# SCH_Cocktail-Hat-Screw-Terminals_2026-04.net
KiCad netlist of a schematic drawn in EasyEDA
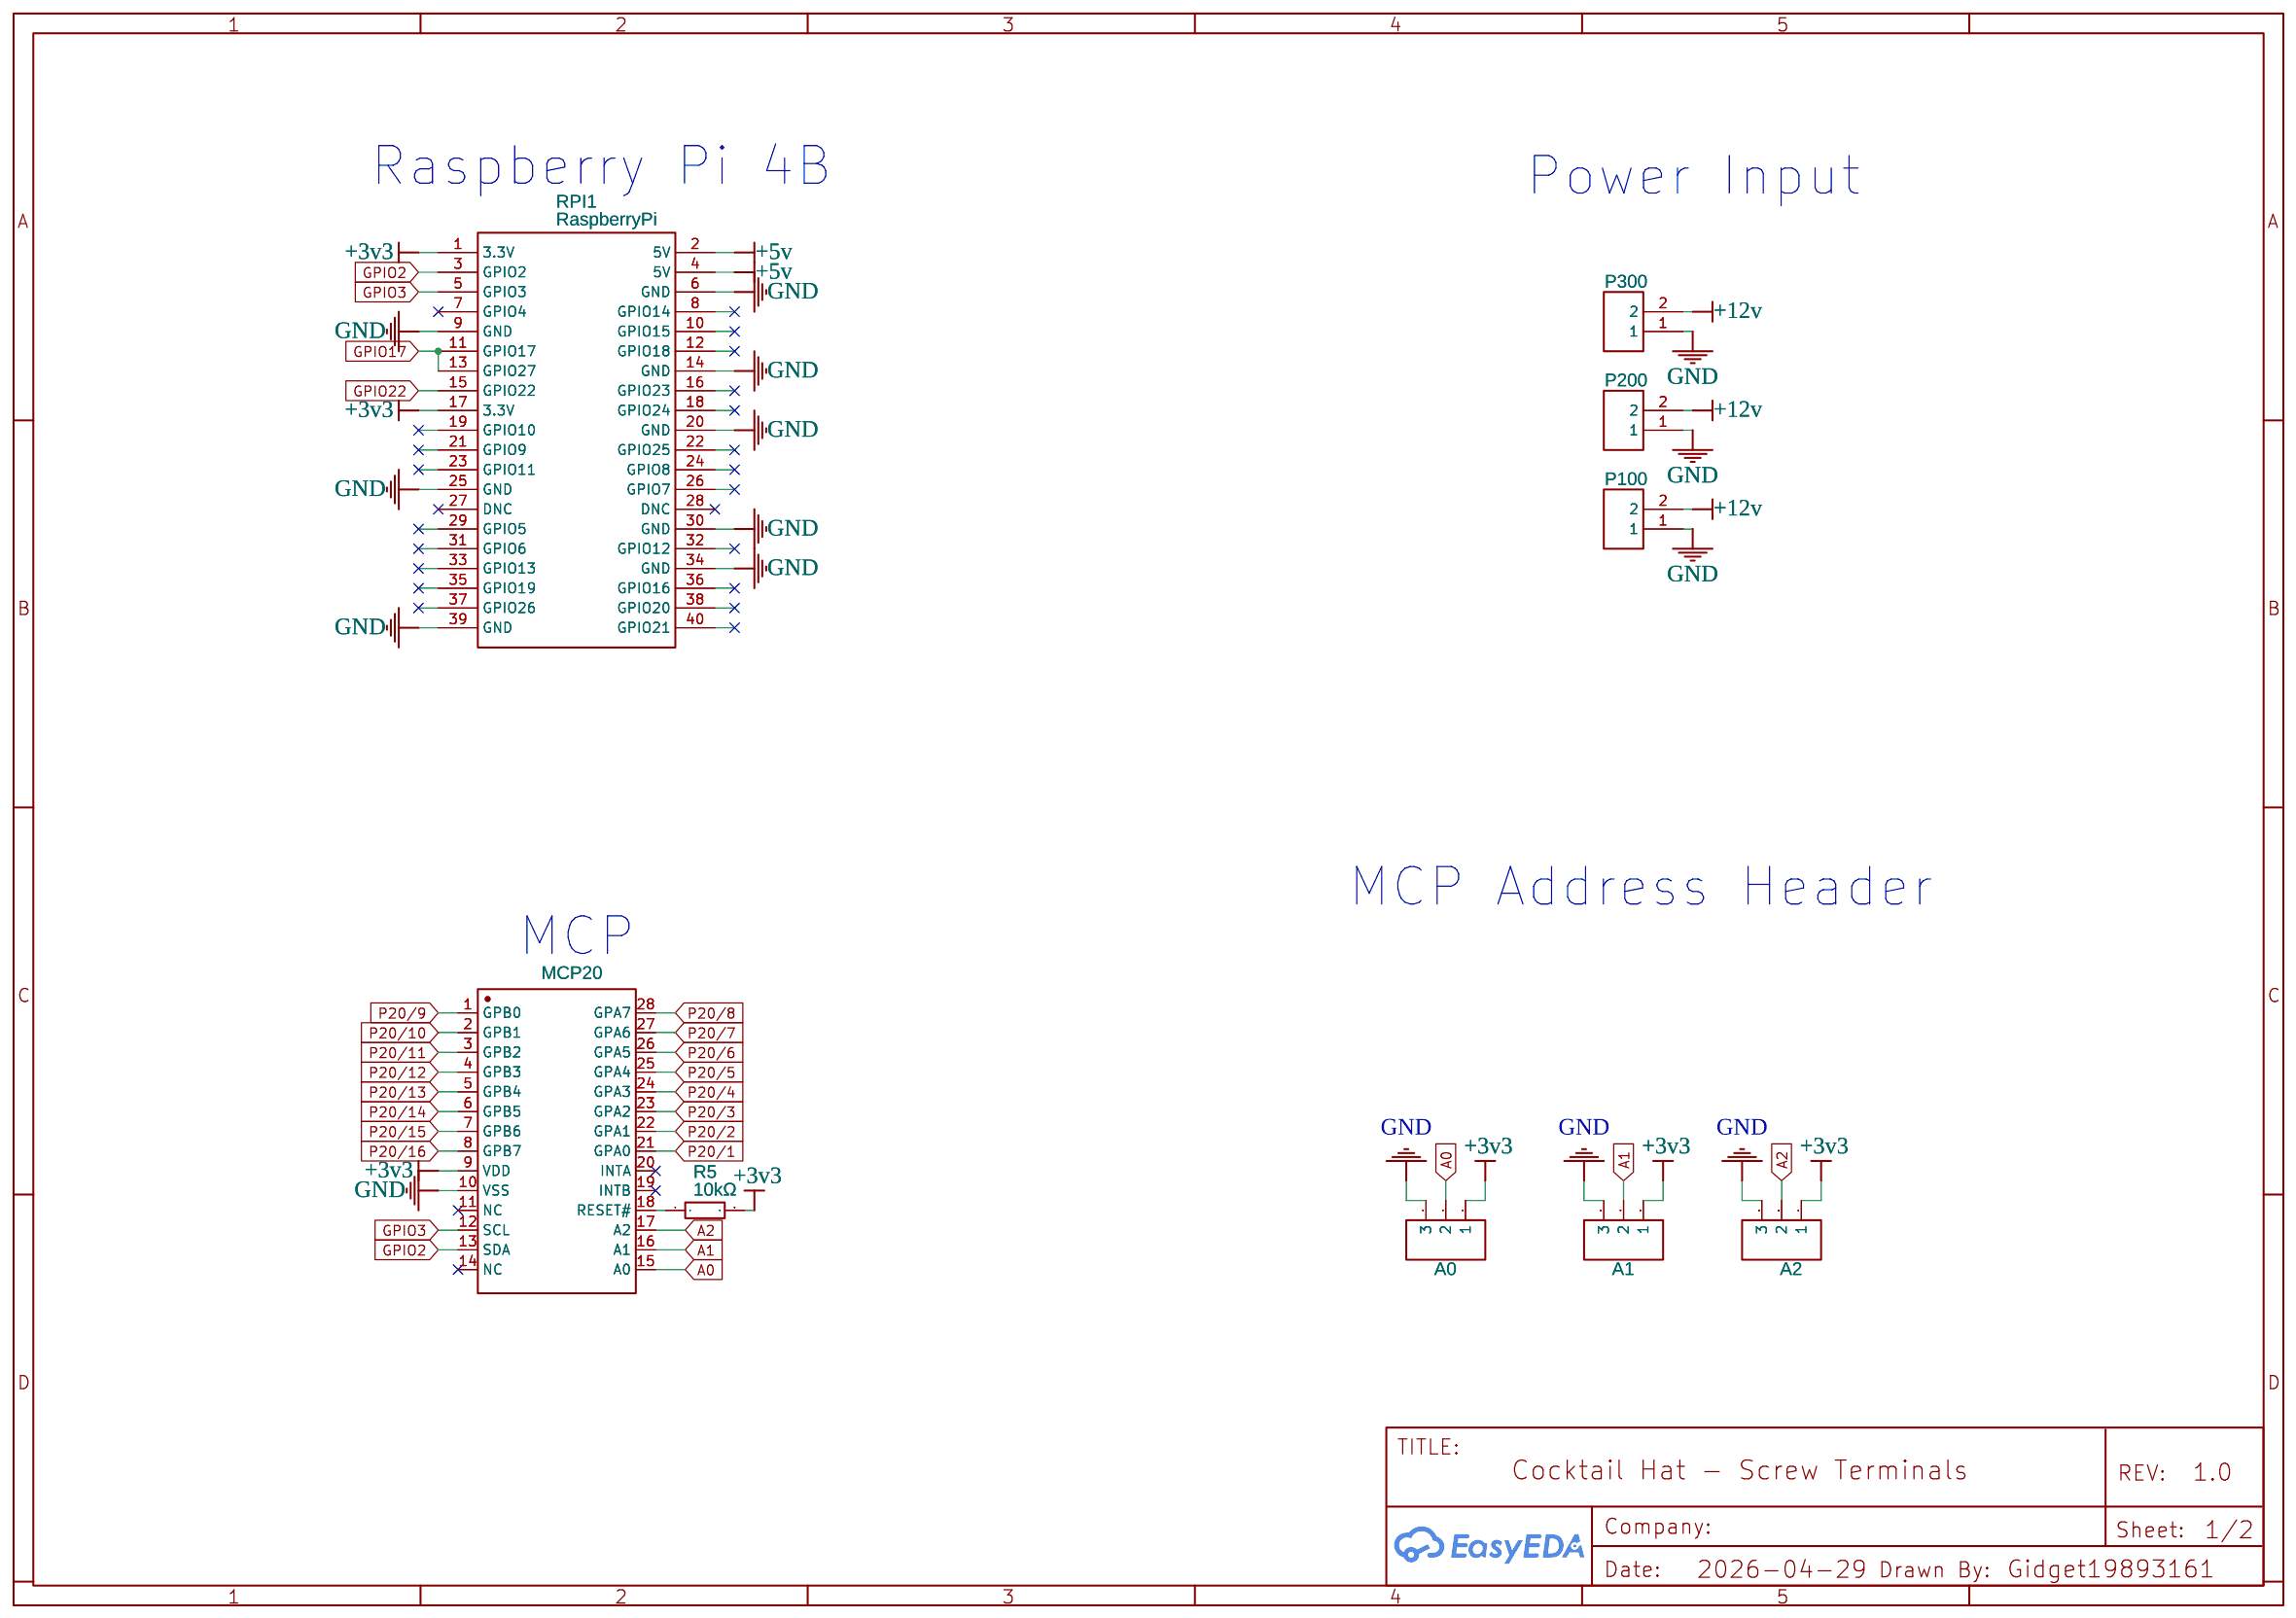
[diagram p0: Main]
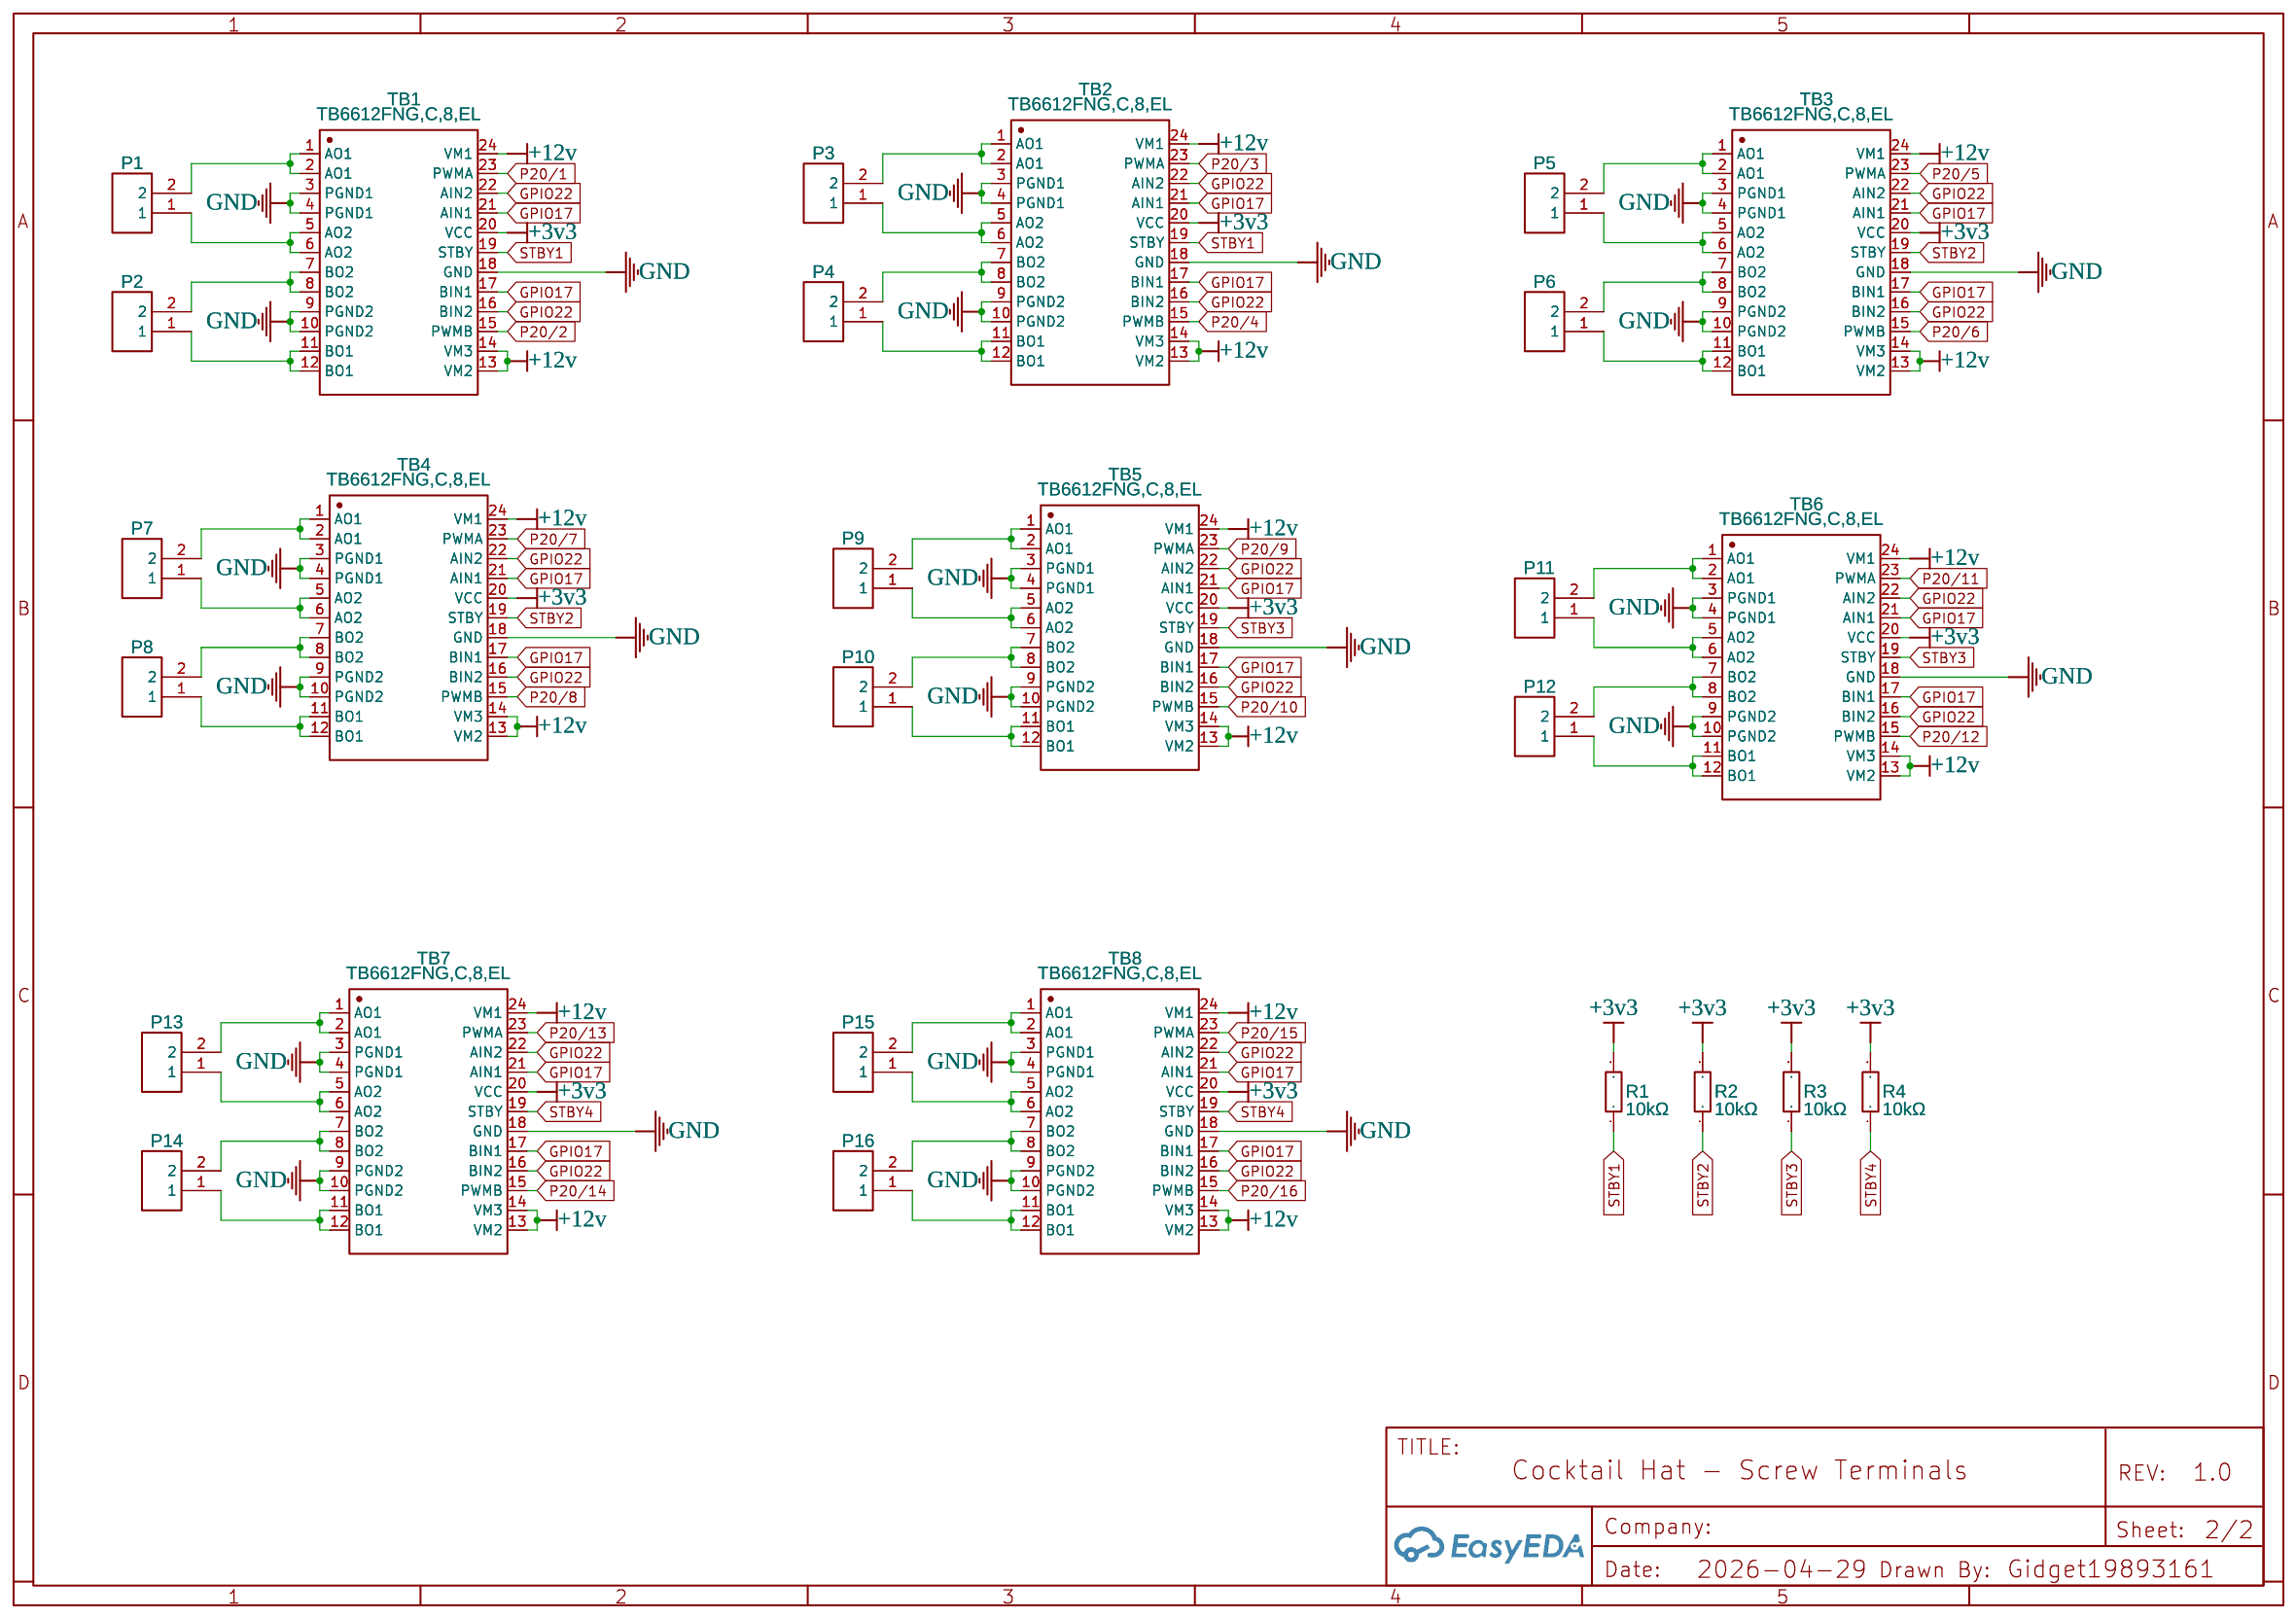
[diagram p1: TB20]

(export (version "E")
  (design (tool "Eeschema 10.0.6"))
  (components
    (comp (ref "A0")
      (value "Header-Male-2.54_1x3")
      (fields (field (name "Manufacturer Part") "2.54-1*3P针") (field (name "Manufacturer") "BOOMELE(博穆精密)"))
      (libsource (lib "") (part "Header-Male-2.54_1x3"))
    )
    (comp (ref "A1")
      (value "Header-Male-2.54_1x3")
      (fields (field (name "Manufacturer Part") "2.54-1*3P针") (field (name "Manufacturer") "BOOMELE(博穆精密)"))
      (libsource (lib "") (part "Header-Male-2.54_1x3"))
    )
    (comp (ref "A2")
      (value "Header-Male-2.54_1x3")
      (fields (field (name "Manufacturer Part") "2.54-1*3P针") (field (name "Manufacturer") "BOOMELE(博穆精密)"))
      (libsource (lib "") (part "Header-Male-2.54_1x3"))
    )
    (comp (ref "MCP20")
      (value "MCP23017-E/SO")
      (fields (field (name "Manufacturer") "MICROCHIP(美国微芯)"))
      (libsource (lib "") (part "MCP23017-E/SO"))
    )
    (comp (ref "P100")
      (value "WJ500V-5.08-2P-14-00A")
      (fields
        (field (name "Manufacturer Part") "WJ500V-5.08-2P")
        (field (name "Manufacturer") "KANGNEX(康奈克斯电气)")
      )
      (libsource (lib "") (part "WJ500V-5.08-2P-14-00A"))
    )
    (comp (ref "P200")
      (value "WJ500V-5.08-2P-14-00A")
      (fields
        (field (name "Manufacturer Part") "WJ500V-5.08-2P")
        (field (name "Manufacturer") "KANGNEX(康奈克斯电气)")
      )
      (libsource (lib "") (part "WJ500V-5.08-2P-14-00A"))
    )
    (comp (ref "P300")
      (value "WJ500V-5.08-2P-14-00A")
      (fields
        (field (name "Manufacturer Part") "WJ500V-5.08-2P")
        (field (name "Manufacturer") "KANGNEX(康奈克斯电气)")
      )
      (libsource (lib "") (part "WJ500V-5.08-2P-14-00A"))
    )
    (comp (ref "R5")
      (value "10kΩ")
      (fields
        (field (name "Manufacturer Part") "1206W4F1002T5E")
        (field (name "Manufacturer") "UNI-ROYAL(厚声)")
      )
      (libsource (lib "") (part "1206W4F1002T5E"))
    )
    (comp (ref "RPI1") (value "RaspberryPi") (libsource (lib "") (part "RaspberryPi")))
    (comp (ref "P1")
      (value "WJ500V-5.08-2P-14-00A")
      (fields
        (field (name "Manufacturer Part") "WJ500V-5.08-2P")
        (field (name "Manufacturer") "KANGNEX(康奈克斯电气)")
      )
      (libsource (lib "") (part "WJ500V-5.08-2P-14-00A"))
    )
    (comp (ref "P2")
      (value "WJ500V-5.08-2P-14-00A")
      (fields
        (field (name "Manufacturer Part") "WJ500V-5.08-2P")
        (field (name "Manufacturer") "KANGNEX(康奈克斯电气)")
      )
      (libsource (lib "") (part "WJ500V-5.08-2P-14-00A"))
    )
    (comp (ref "P3")
      (value "WJ500V-5.08-2P-14-00A")
      (fields
        (field (name "Manufacturer Part") "WJ500V-5.08-2P")
        (field (name "Manufacturer") "KANGNEX(康奈克斯电气)")
      )
      (libsource (lib "") (part "WJ500V-5.08-2P-14-00A"))
    )
    (comp (ref "P4")
      (value "WJ500V-5.08-2P-14-00A")
      (fields
        (field (name "Manufacturer Part") "WJ500V-5.08-2P")
        (field (name "Manufacturer") "KANGNEX(康奈克斯电气)")
      )
      (libsource (lib "") (part "WJ500V-5.08-2P-14-00A"))
    )
    (comp (ref "P5")
      (value "WJ500V-5.08-2P-14-00A")
      (fields
        (field (name "Manufacturer Part") "WJ500V-5.08-2P")
        (field (name "Manufacturer") "KANGNEX(康奈克斯电气)")
      )
      (libsource (lib "") (part "WJ500V-5.08-2P-14-00A"))
    )
    (comp (ref "P6")
      (value "WJ500V-5.08-2P-14-00A")
      (fields
        (field (name "Manufacturer Part") "WJ500V-5.08-2P")
        (field (name "Manufacturer") "KANGNEX(康奈克斯电气)")
      )
      (libsource (lib "") (part "WJ500V-5.08-2P-14-00A"))
    )
    (comp (ref "P7")
      (value "WJ500V-5.08-2P-14-00A")
      (fields
        (field (name "Manufacturer Part") "WJ500V-5.08-2P")
        (field (name "Manufacturer") "KANGNEX(康奈克斯电气)")
      )
      (libsource (lib "") (part "WJ500V-5.08-2P-14-00A"))
    )
    (comp (ref "P8")
      (value "WJ500V-5.08-2P-14-00A")
      (fields
        (field (name "Manufacturer Part") "WJ500V-5.08-2P")
        (field (name "Manufacturer") "KANGNEX(康奈克斯电气)")
      )
      (libsource (lib "") (part "WJ500V-5.08-2P-14-00A"))
    )
    (comp (ref "P9")
      (value "WJ500V-5.08-2P-14-00A")
      (fields
        (field (name "Manufacturer Part") "WJ500V-5.08-2P")
        (field (name "Manufacturer") "KANGNEX(康奈克斯电气)")
      )
      (libsource (lib "") (part "WJ500V-5.08-2P-14-00A"))
    )
    (comp (ref "P10")
      (value "WJ500V-5.08-2P-14-00A")
      (fields
        (field (name "Manufacturer Part") "WJ500V-5.08-2P")
        (field (name "Manufacturer") "KANGNEX(康奈克斯电气)")
      )
      (libsource (lib "") (part "WJ500V-5.08-2P-14-00A"))
    )
    (comp (ref "P11")
      (value "WJ500V-5.08-2P-14-00A")
      (fields
        (field (name "Manufacturer Part") "WJ500V-5.08-2P")
        (field (name "Manufacturer") "KANGNEX(康奈克斯电气)")
      )
      (libsource (lib "") (part "WJ500V-5.08-2P-14-00A"))
    )
    (comp (ref "P12")
      (value "WJ500V-5.08-2P-14-00A")
      (fields
        (field (name "Manufacturer Part") "WJ500V-5.08-2P")
        (field (name "Manufacturer") "KANGNEX(康奈克斯电气)")
      )
      (libsource (lib "") (part "WJ500V-5.08-2P-14-00A"))
    )
    (comp (ref "P13")
      (value "WJ500V-5.08-2P-14-00A")
      (fields
        (field (name "Manufacturer Part") "WJ500V-5.08-2P")
        (field (name "Manufacturer") "KANGNEX(康奈克斯电气)")
      )
      (libsource (lib "") (part "WJ500V-5.08-2P-14-00A"))
    )
    (comp (ref "P14")
      (value "WJ500V-5.08-2P-14-00A")
      (fields
        (field (name "Manufacturer Part") "WJ500V-5.08-2P")
        (field (name "Manufacturer") "KANGNEX(康奈克斯电气)")
      )
      (libsource (lib "") (part "WJ500V-5.08-2P-14-00A"))
    )
    (comp (ref "P15")
      (value "WJ500V-5.08-2P-14-00A")
      (fields
        (field (name "Manufacturer Part") "WJ500V-5.08-2P")
        (field (name "Manufacturer") "KANGNEX(康奈克斯电气)")
      )
      (libsource (lib "") (part "WJ500V-5.08-2P-14-00A"))
    )
    (comp (ref "P16")
      (value "WJ500V-5.08-2P-14-00A")
      (fields
        (field (name "Manufacturer Part") "WJ500V-5.08-2P")
        (field (name "Manufacturer") "KANGNEX(康奈克斯电气)")
      )
      (libsource (lib "") (part "WJ500V-5.08-2P-14-00A"))
    )
    (comp (ref "R1")
      (value "10kΩ")
      (fields
        (field (name "Manufacturer Part") "1206W4F1002T5E")
        (field (name "Manufacturer") "UNI-ROYAL(厚声)")
      )
      (libsource (lib "") (part "1206W4F1002T5E"))
    )
    (comp (ref "R2")
      (value "10kΩ")
      (fields
        (field (name "Manufacturer Part") "1206W4F1002T5E")
        (field (name "Manufacturer") "UNI-ROYAL(厚声)")
      )
      (libsource (lib "") (part "1206W4F1002T5E"))
    )
    (comp (ref "R3")
      (value "10kΩ")
      (fields
        (field (name "Manufacturer Part") "1206W4F1002T5E")
        (field (name "Manufacturer") "UNI-ROYAL(厚声)")
      )
      (libsource (lib "") (part "1206W4F1002T5E"))
    )
    (comp (ref "R4")
      (value "10kΩ")
      (fields
        (field (name "Manufacturer Part") "1206W4F1002T5E")
        (field (name "Manufacturer") "UNI-ROYAL(厚声)")
      )
      (libsource (lib "") (part "1206W4F1002T5E"))
    )
    (comp (ref "TB1")
      (value "TB6612FNG,C,8,EL")
      (fields (field (name "Manufacturer") "TOSHIBA(东芝)"))
      (libsource (lib "") (part "TB6612FNG,C,8,EL"))
    )
    (comp (ref "TB2")
      (value "TB6612FNG,C,8,EL")
      (fields (field (name "Manufacturer") "TOSHIBA(东芝)"))
      (libsource (lib "") (part "TB6612FNG,C,8,EL"))
    )
    (comp (ref "TB3")
      (value "TB6612FNG,C,8,EL")
      (fields (field (name "Manufacturer") "TOSHIBA(东芝)"))
      (libsource (lib "") (part "TB6612FNG,C,8,EL"))
    )
    (comp (ref "TB4")
      (value "TB6612FNG,C,8,EL")
      (fields (field (name "Manufacturer") "TOSHIBA(东芝)"))
      (libsource (lib "") (part "TB6612FNG,C,8,EL"))
    )
    (comp (ref "TB5")
      (value "TB6612FNG,C,8,EL")
      (fields (field (name "Manufacturer") "TOSHIBA(东芝)"))
      (libsource (lib "") (part "TB6612FNG,C,8,EL"))
    )
    (comp (ref "TB6")
      (value "TB6612FNG,C,8,EL")
      (fields (field (name "Manufacturer") "TOSHIBA(东芝)"))
      (libsource (lib "") (part "TB6612FNG,C,8,EL"))
    )
    (comp (ref "TB7")
      (value "TB6612FNG,C,8,EL")
      (fields (field (name "Manufacturer") "TOSHIBA(东芝)"))
      (libsource (lib "") (part "TB6612FNG,C,8,EL"))
    )
    (comp (ref "TB8")
      (value "TB6612FNG,C,8,EL")
      (fields (field (name "Manufacturer") "TOSHIBA(东芝)"))
      (libsource (lib "") (part "TB6612FNG,C,8,EL"))
    )
  )
  (nets
    (net (code "1") (name "+3v3") (class "Default")
      (node (ref "A0") (pin "1") (pinfunction "1_1") (pintype "input"))
      (node (ref "A1") (pin "1") (pinfunction "1_1") (pintype "input"))
      (node (ref "A2") (pin "1") (pinfunction "1_1") (pintype "input"))
      (node (ref "MCP20") (pin "9") (pinfunction "VDD_9") (pintype "unspecified"))
      (node (ref "R1") (pin "2") (pinfunction "2_2") (pintype "input"))
      (node (ref "R2") (pin "2") (pinfunction "2_2") (pintype "input"))
      (node (ref "R3") (pin "2") (pinfunction "2_2") (pintype "input"))
      (node (ref "R4") (pin "2") (pinfunction "2_2") (pintype "input"))
      (node (ref "R5") (pin "2") (pinfunction "2_2") (pintype "input"))
      (node (ref "RPI1") (pin "1") (pinfunction "3.3V_1") (pintype "unspecified"))
      (node (ref "RPI1") (pin "17") (pinfunction "3.3V_17") (pintype "unspecified"))
      (node (ref "TB1") (pin "20") (pinfunction "VCC_20") (pintype "unspecified"))
      (node (ref "TB2") (pin "20") (pinfunction "VCC_20") (pintype "unspecified"))
      (node (ref "TB3") (pin "20") (pinfunction "VCC_20") (pintype "unspecified"))
      (node (ref "TB4") (pin "20") (pinfunction "VCC_20") (pintype "unspecified"))
      (node (ref "TB5") (pin "20") (pinfunction "VCC_20") (pintype "unspecified"))
      (node (ref "TB6") (pin "20") (pinfunction "VCC_20") (pintype "unspecified"))
      (node (ref "TB7") (pin "20") (pinfunction "VCC_20") (pintype "unspecified"))
      (node (ref "TB8") (pin "20") (pinfunction "VCC_20") (pintype "unspecified"))
    )
    (net (code "2") (name "+5v") (class "Default")
      (node (ref "RPI1") (pin "2") (pinfunction "5V_2") (pintype "unspecified"))
      (node (ref "RPI1") (pin "4") (pinfunction "5V_4") (pintype "unspecified"))
    )
    (net (code "3") (name "+12v") (class "Default")
      (node (ref "P100") (pin "2") (pinfunction "2_2") (pintype "unspecified"))
      (node (ref "P200") (pin "2") (pinfunction "2_2") (pintype "unspecified"))
      (node (ref "P300") (pin "2") (pinfunction "2_2") (pintype "unspecified"))
      (node (ref "TB1") (pin "13") (pinfunction "VM2_13") (pintype "unspecified"))
      (node (ref "TB1") (pin "14") (pinfunction "VM3_14") (pintype "unspecified"))
      (node (ref "TB1") (pin "24") (pinfunction "VM1_24") (pintype "unspecified"))
      (node (ref "TB2") (pin "13") (pinfunction "VM2_13") (pintype "unspecified"))
      (node (ref "TB2") (pin "14") (pinfunction "VM3_14") (pintype "unspecified"))
      (node (ref "TB2") (pin "24") (pinfunction "VM1_24") (pintype "unspecified"))
      (node (ref "TB3") (pin "13") (pinfunction "VM2_13") (pintype "unspecified"))
      (node (ref "TB3") (pin "14") (pinfunction "VM3_14") (pintype "unspecified"))
      (node (ref "TB3") (pin "24") (pinfunction "VM1_24") (pintype "unspecified"))
      (node (ref "TB4") (pin "13") (pinfunction "VM2_13") (pintype "unspecified"))
      (node (ref "TB4") (pin "14") (pinfunction "VM3_14") (pintype "unspecified"))
      (node (ref "TB4") (pin "24") (pinfunction "VM1_24") (pintype "unspecified"))
      (node (ref "TB5") (pin "13") (pinfunction "VM2_13") (pintype "unspecified"))
      (node (ref "TB5") (pin "14") (pinfunction "VM3_14") (pintype "unspecified"))
      (node (ref "TB5") (pin "24") (pinfunction "VM1_24") (pintype "unspecified"))
      (node (ref "TB6") (pin "13") (pinfunction "VM2_13") (pintype "unspecified"))
      (node (ref "TB6") (pin "14") (pinfunction "VM3_14") (pintype "unspecified"))
      (node (ref "TB6") (pin "24") (pinfunction "VM1_24") (pintype "unspecified"))
      (node (ref "TB7") (pin "13") (pinfunction "VM2_13") (pintype "unspecified"))
      (node (ref "TB7") (pin "14") (pinfunction "VM3_14") (pintype "unspecified"))
      (node (ref "TB7") (pin "24") (pinfunction "VM1_24") (pintype "unspecified"))
      (node (ref "TB8") (pin "13") (pinfunction "VM2_13") (pintype "unspecified"))
      (node (ref "TB8") (pin "14") (pinfunction "VM3_14") (pintype "unspecified"))
      (node (ref "TB8") (pin "24") (pinfunction "VM1_24") (pintype "unspecified"))
    )
    (net (code "4") (name "A0") (class "Default")
      (node (ref "A0") (pin "2") (pinfunction "2_2") (pintype "input"))
      (node (ref "MCP20") (pin "15") (pinfunction "A0_15") (pintype "unspecified"))
    )
    (net (code "5") (name "A1") (class "Default")
      (node (ref "A1") (pin "2") (pinfunction "2_2") (pintype "input"))
      (node (ref "MCP20") (pin "16") (pinfunction "A1_16") (pintype "unspecified"))
    )
    (net (code "6") (name "A2") (class "Default")
      (node (ref "A2") (pin "2") (pinfunction "2_2") (pintype "input"))
      (node (ref "MCP20") (pin "17") (pinfunction "A2_17") (pintype "unspecified"))
    )
    (net (code "7") (name "GND") (class "Default")
      (node (ref "A0") (pin "3") (pinfunction "3_3") (pintype "input"))
      (node (ref "A1") (pin "3") (pinfunction "3_3") (pintype "input"))
      (node (ref "A2") (pin "3") (pinfunction "3_3") (pintype "input"))
      (node (ref "MCP20") (pin "10") (pinfunction "VSS_10") (pintype "unspecified"))
      (node (ref "P100") (pin "1") (pinfunction "1_1") (pintype "unspecified"))
      (node (ref "P200") (pin "1") (pinfunction "1_1") (pintype "unspecified"))
      (node (ref "P300") (pin "1") (pinfunction "1_1") (pintype "unspecified"))
      (node (ref "RPI1") (pin "14") (pinfunction "GND_14") (pintype "unspecified"))
      (node (ref "RPI1") (pin "20") (pinfunction "GND_20") (pintype "unspecified"))
      (node (ref "RPI1") (pin "25") (pinfunction "GND_25") (pintype "unspecified"))
      (node (ref "RPI1") (pin "30") (pinfunction "GND_30") (pintype "unspecified"))
      (node (ref "RPI1") (pin "34") (pinfunction "GND_34") (pintype "unspecified"))
      (node (ref "RPI1") (pin "39") (pinfunction "GND_39") (pintype "unspecified"))
      (node (ref "RPI1") (pin "6") (pinfunction "GND_6") (pintype "unspecified"))
      (node (ref "RPI1") (pin "9") (pinfunction "GND_9") (pintype "unspecified"))
      (node (ref "TB1") (pin "10") (pinfunction "PGND2_10") (pintype "unspecified"))
      (node (ref "TB1") (pin "18") (pinfunction "GND_18") (pintype "unspecified"))
      (node (ref "TB1") (pin "3") (pinfunction "PGND1_3") (pintype "unspecified"))
      (node (ref "TB1") (pin "4") (pinfunction "PGND1_4") (pintype "unspecified"))
      (node (ref "TB1") (pin "9") (pinfunction "PGND2_9") (pintype "unspecified"))
      (node (ref "TB2") (pin "10") (pinfunction "PGND2_10") (pintype "unspecified"))
      (node (ref "TB2") (pin "18") (pinfunction "GND_18") (pintype "unspecified"))
      (node (ref "TB2") (pin "3") (pinfunction "PGND1_3") (pintype "unspecified"))
      (node (ref "TB2") (pin "4") (pinfunction "PGND1_4") (pintype "unspecified"))
      (node (ref "TB2") (pin "9") (pinfunction "PGND2_9") (pintype "unspecified"))
      (node (ref "TB3") (pin "10") (pinfunction "PGND2_10") (pintype "unspecified"))
      (node (ref "TB3") (pin "18") (pinfunction "GND_18") (pintype "unspecified"))
      (node (ref "TB3") (pin "3") (pinfunction "PGND1_3") (pintype "unspecified"))
      (node (ref "TB3") (pin "4") (pinfunction "PGND1_4") (pintype "unspecified"))
      (node (ref "TB3") (pin "9") (pinfunction "PGND2_9") (pintype "unspecified"))
      (node (ref "TB4") (pin "10") (pinfunction "PGND2_10") (pintype "unspecified"))
      (node (ref "TB4") (pin "18") (pinfunction "GND_18") (pintype "unspecified"))
      (node (ref "TB4") (pin "3") (pinfunction "PGND1_3") (pintype "unspecified"))
      (node (ref "TB4") (pin "4") (pinfunction "PGND1_4") (pintype "unspecified"))
      (node (ref "TB4") (pin "9") (pinfunction "PGND2_9") (pintype "unspecified"))
      (node (ref "TB5") (pin "10") (pinfunction "PGND2_10") (pintype "unspecified"))
      (node (ref "TB5") (pin "18") (pinfunction "GND_18") (pintype "unspecified"))
      (node (ref "TB5") (pin "3") (pinfunction "PGND1_3") (pintype "unspecified"))
      (node (ref "TB5") (pin "4") (pinfunction "PGND1_4") (pintype "unspecified"))
      (node (ref "TB5") (pin "9") (pinfunction "PGND2_9") (pintype "unspecified"))
      (node (ref "TB6") (pin "10") (pinfunction "PGND2_10") (pintype "unspecified"))
      (node (ref "TB6") (pin "18") (pinfunction "GND_18") (pintype "unspecified"))
      (node (ref "TB6") (pin "3") (pinfunction "PGND1_3") (pintype "unspecified"))
      (node (ref "TB6") (pin "4") (pinfunction "PGND1_4") (pintype "unspecified"))
      (node (ref "TB6") (pin "9") (pinfunction "PGND2_9") (pintype "unspecified"))
      (node (ref "TB7") (pin "10") (pinfunction "PGND2_10") (pintype "unspecified"))
      (node (ref "TB7") (pin "18") (pinfunction "GND_18") (pintype "unspecified"))
      (node (ref "TB7") (pin "3") (pinfunction "PGND1_3") (pintype "unspecified"))
      (node (ref "TB7") (pin "4") (pinfunction "PGND1_4") (pintype "unspecified"))
      (node (ref "TB7") (pin "9") (pinfunction "PGND2_9") (pintype "unspecified"))
      (node (ref "TB8") (pin "10") (pinfunction "PGND2_10") (pintype "unspecified"))
      (node (ref "TB8") (pin "18") (pinfunction "GND_18") (pintype "unspecified"))
      (node (ref "TB8") (pin "3") (pinfunction "PGND1_3") (pintype "unspecified"))
      (node (ref "TB8") (pin "4") (pinfunction "PGND1_4") (pintype "unspecified"))
      (node (ref "TB8") (pin "9") (pinfunction "PGND2_9") (pintype "unspecified"))
    )
    (net (code "8") (name "GPIO2") (class "Default")
      (node (ref "MCP20") (pin "13") (pinfunction "SDA_13") (pintype "unspecified"))
      (node (ref "RPI1") (pin "3") (pinfunction "GPIO2_3") (pintype "unspecified"))
    )
    (net (code "9") (name "GPIO3") (class "Default")
      (node (ref "MCP20") (pin "12") (pinfunction "SCL_12") (pintype "unspecified"))
      (node (ref "RPI1") (pin "5") (pinfunction "GPIO3_5") (pintype "unspecified"))
    )
    (net (code "10") (name "GPIO17") (class "Default")
      (node (ref "RPI1") (pin "11") (pinfunction "GPIO17_11") (pintype "unspecified"))
      (node (ref "RPI1") (pin "13") (pinfunction "GPIO27_13") (pintype "unspecified"))
      (node (ref "TB1") (pin "17") (pinfunction "BIN1_17") (pintype "unspecified"))
      (node (ref "TB1") (pin "21") (pinfunction "AIN1_21") (pintype "unspecified"))
      (node (ref "TB2") (pin "17") (pinfunction "BIN1_17") (pintype "unspecified"))
      (node (ref "TB2") (pin "21") (pinfunction "AIN1_21") (pintype "unspecified"))
      (node (ref "TB3") (pin "17") (pinfunction "BIN1_17") (pintype "unspecified"))
      (node (ref "TB3") (pin "21") (pinfunction "AIN1_21") (pintype "unspecified"))
      (node (ref "TB4") (pin "17") (pinfunction "BIN1_17") (pintype "unspecified"))
      (node (ref "TB4") (pin "21") (pinfunction "AIN1_21") (pintype "unspecified"))
      (node (ref "TB5") (pin "17") (pinfunction "BIN1_17") (pintype "unspecified"))
      (node (ref "TB5") (pin "21") (pinfunction "AIN1_21") (pintype "unspecified"))
      (node (ref "TB6") (pin "17") (pinfunction "BIN1_17") (pintype "unspecified"))
      (node (ref "TB6") (pin "21") (pinfunction "AIN1_21") (pintype "unspecified"))
      (node (ref "TB7") (pin "17") (pinfunction "BIN1_17") (pintype "unspecified"))
      (node (ref "TB7") (pin "21") (pinfunction "AIN1_21") (pintype "unspecified"))
      (node (ref "TB8") (pin "17") (pinfunction "BIN1_17") (pintype "unspecified"))
      (node (ref "TB8") (pin "21") (pinfunction "AIN1_21") (pintype "unspecified"))
    )
    (net (code "11") (name "GPIO22") (class "Default")
      (node (ref "RPI1") (pin "15") (pinfunction "GPIO22_15") (pintype "unspecified"))
      (node (ref "TB1") (pin "16") (pinfunction "BIN2_16") (pintype "unspecified"))
      (node (ref "TB1") (pin "22") (pinfunction "AIN2_22") (pintype "unspecified"))
      (node (ref "TB2") (pin "16") (pinfunction "BIN2_16") (pintype "unspecified"))
      (node (ref "TB2") (pin "22") (pinfunction "AIN2_22") (pintype "unspecified"))
      (node (ref "TB3") (pin "16") (pinfunction "BIN2_16") (pintype "unspecified"))
      (node (ref "TB3") (pin "22") (pinfunction "AIN2_22") (pintype "unspecified"))
      (node (ref "TB4") (pin "16") (pinfunction "BIN2_16") (pintype "unspecified"))
      (node (ref "TB4") (pin "22") (pinfunction "AIN2_22") (pintype "unspecified"))
      (node (ref "TB5") (pin "16") (pinfunction "BIN2_16") (pintype "unspecified"))
      (node (ref "TB5") (pin "22") (pinfunction "AIN2_22") (pintype "unspecified"))
      (node (ref "TB6") (pin "16") (pinfunction "BIN2_16") (pintype "unspecified"))
      (node (ref "TB6") (pin "22") (pinfunction "AIN2_22") (pintype "unspecified"))
      (node (ref "TB7") (pin "16") (pinfunction "BIN2_16") (pintype "unspecified"))
      (node (ref "TB7") (pin "22") (pinfunction "AIN2_22") (pintype "unspecified"))
      (node (ref "TB8") (pin "16") (pinfunction "BIN2_16") (pintype "unspecified"))
      (node (ref "TB8") (pin "22") (pinfunction "AIN2_22") (pintype "unspecified"))
    )
    (net (code "12") (name "Net-(MCP20-RESET#)") (class "Default")
      (node (ref "MCP20") (pin "18") (pinfunction "RESET#_18") (pintype "unspecified"))
      (node (ref "R5") (pin "1") (pinfunction "1_1") (pintype "input"))
    )
    (net (code "13") (name "Net-(P1-Pad1)") (class "Default")
      (node (ref "P1") (pin "1") (pinfunction "1_1") (pintype "unspecified"))
      (node (ref "TB1") (pin "5") (pinfunction "AO2_5") (pintype "unspecified"))
      (node (ref "TB1") (pin "6") (pinfunction "AO2_6") (pintype "unspecified"))
    )
    (net (code "14") (name "Net-(P1-Pad2)") (class "Default")
      (node (ref "P1") (pin "2") (pinfunction "2_2") (pintype "unspecified"))
      (node (ref "TB1") (pin "1") (pinfunction "AO1_1") (pintype "unspecified"))
      (node (ref "TB1") (pin "2") (pinfunction "AO1_2") (pintype "unspecified"))
    )
    (net (code "15") (name "Net-(P2-Pad1)") (class "Default")
      (node (ref "P2") (pin "1") (pinfunction "1_1") (pintype "unspecified"))
      (node (ref "TB1") (pin "11") (pinfunction "BO1_11") (pintype "unspecified"))
      (node (ref "TB1") (pin "12") (pinfunction "BO1_12") (pintype "unspecified"))
    )
    (net (code "16") (name "Net-(P2-Pad2)") (class "Default")
      (node (ref "P2") (pin "2") (pinfunction "2_2") (pintype "unspecified"))
      (node (ref "TB1") (pin "7") (pinfunction "BO2_7") (pintype "unspecified"))
      (node (ref "TB1") (pin "8") (pinfunction "BO2_8") (pintype "unspecified"))
    )
    (net (code "17") (name "Net-(P3-Pad1)") (class "Default")
      (node (ref "P3") (pin "1") (pinfunction "1_1") (pintype "unspecified"))
      (node (ref "TB2") (pin "5") (pinfunction "AO2_5") (pintype "unspecified"))
      (node (ref "TB2") (pin "6") (pinfunction "AO2_6") (pintype "unspecified"))
    )
    (net (code "18") (name "Net-(P3-Pad2)") (class "Default")
      (node (ref "P3") (pin "2") (pinfunction "2_2") (pintype "unspecified"))
      (node (ref "TB2") (pin "1") (pinfunction "AO1_1") (pintype "unspecified"))
      (node (ref "TB2") (pin "2") (pinfunction "AO1_2") (pintype "unspecified"))
    )
    (net (code "19") (name "Net-(P4-Pad1)") (class "Default")
      (node (ref "P4") (pin "1") (pinfunction "1_1") (pintype "unspecified"))
      (node (ref "TB2") (pin "11") (pinfunction "BO1_11") (pintype "unspecified"))
      (node (ref "TB2") (pin "12") (pinfunction "BO1_12") (pintype "unspecified"))
    )
    (net (code "20") (name "Net-(P4-Pad2)") (class "Default")
      (node (ref "P4") (pin "2") (pinfunction "2_2") (pintype "unspecified"))
      (node (ref "TB2") (pin "7") (pinfunction "BO2_7") (pintype "unspecified"))
      (node (ref "TB2") (pin "8") (pinfunction "BO2_8") (pintype "unspecified"))
    )
    (net (code "21") (name "Net-(P5-Pad1)") (class "Default")
      (node (ref "P5") (pin "1") (pinfunction "1_1") (pintype "unspecified"))
      (node (ref "TB3") (pin "5") (pinfunction "AO2_5") (pintype "unspecified"))
      (node (ref "TB3") (pin "6") (pinfunction "AO2_6") (pintype "unspecified"))
    )
    (net (code "22") (name "Net-(P5-Pad2)") (class "Default")
      (node (ref "P5") (pin "2") (pinfunction "2_2") (pintype "unspecified"))
      (node (ref "TB3") (pin "1") (pinfunction "AO1_1") (pintype "unspecified"))
      (node (ref "TB3") (pin "2") (pinfunction "AO1_2") (pintype "unspecified"))
    )
    (net (code "23") (name "Net-(P6-Pad1)") (class "Default")
      (node (ref "P6") (pin "1") (pinfunction "1_1") (pintype "unspecified"))
      (node (ref "TB3") (pin "11") (pinfunction "BO1_11") (pintype "unspecified"))
      (node (ref "TB3") (pin "12") (pinfunction "BO1_12") (pintype "unspecified"))
    )
    (net (code "24") (name "Net-(P6-Pad2)") (class "Default")
      (node (ref "P6") (pin "2") (pinfunction "2_2") (pintype "unspecified"))
      (node (ref "TB3") (pin "7") (pinfunction "BO2_7") (pintype "unspecified"))
      (node (ref "TB3") (pin "8") (pinfunction "BO2_8") (pintype "unspecified"))
    )
    (net (code "25") (name "Net-(P7-Pad1)") (class "Default")
      (node (ref "P7") (pin "1") (pinfunction "1_1") (pintype "unspecified"))
      (node (ref "TB4") (pin "5") (pinfunction "AO2_5") (pintype "unspecified"))
      (node (ref "TB4") (pin "6") (pinfunction "AO2_6") (pintype "unspecified"))
    )
    (net (code "26") (name "Net-(P7-Pad2)") (class "Default")
      (node (ref "P7") (pin "2") (pinfunction "2_2") (pintype "unspecified"))
      (node (ref "TB4") (pin "1") (pinfunction "AO1_1") (pintype "unspecified"))
      (node (ref "TB4") (pin "2") (pinfunction "AO1_2") (pintype "unspecified"))
    )
    (net (code "27") (name "Net-(P8-Pad1)") (class "Default")
      (node (ref "P8") (pin "1") (pinfunction "1_1") (pintype "unspecified"))
      (node (ref "TB4") (pin "11") (pinfunction "BO1_11") (pintype "unspecified"))
      (node (ref "TB4") (pin "12") (pinfunction "BO1_12") (pintype "unspecified"))
    )
    (net (code "28") (name "Net-(P8-Pad2)") (class "Default")
      (node (ref "P8") (pin "2") (pinfunction "2_2") (pintype "unspecified"))
      (node (ref "TB4") (pin "7") (pinfunction "BO2_7") (pintype "unspecified"))
      (node (ref "TB4") (pin "8") (pinfunction "BO2_8") (pintype "unspecified"))
    )
    (net (code "29") (name "Net-(P9-Pad1)") (class "Default")
      (node (ref "P9") (pin "1") (pinfunction "1_1") (pintype "unspecified"))
      (node (ref "TB5") (pin "5") (pinfunction "AO2_5") (pintype "unspecified"))
      (node (ref "TB5") (pin "6") (pinfunction "AO2_6") (pintype "unspecified"))
    )
    (net (code "30") (name "Net-(P9-Pad2)") (class "Default")
      (node (ref "P9") (pin "2") (pinfunction "2_2") (pintype "unspecified"))
      (node (ref "TB5") (pin "1") (pinfunction "AO1_1") (pintype "unspecified"))
      (node (ref "TB5") (pin "2") (pinfunction "AO1_2") (pintype "unspecified"))
    )
    (net (code "31") (name "Net-(P10-Pad1)") (class "Default")
      (node (ref "P10") (pin "1") (pinfunction "1_1") (pintype "unspecified"))
      (node (ref "TB5") (pin "11") (pinfunction "BO1_11") (pintype "unspecified"))
      (node (ref "TB5") (pin "12") (pinfunction "BO1_12") (pintype "unspecified"))
    )
    (net (code "32") (name "Net-(P10-Pad2)") (class "Default")
      (node (ref "P10") (pin "2") (pinfunction "2_2") (pintype "unspecified"))
      (node (ref "TB5") (pin "7") (pinfunction "BO2_7") (pintype "unspecified"))
      (node (ref "TB5") (pin "8") (pinfunction "BO2_8") (pintype "unspecified"))
    )
    (net (code "33") (name "Net-(P11-Pad1)") (class "Default")
      (node (ref "P11") (pin "1") (pinfunction "1_1") (pintype "unspecified"))
      (node (ref "TB6") (pin "5") (pinfunction "AO2_5") (pintype "unspecified"))
      (node (ref "TB6") (pin "6") (pinfunction "AO2_6") (pintype "unspecified"))
    )
    (net (code "34") (name "Net-(P11-Pad2)") (class "Default")
      (node (ref "P11") (pin "2") (pinfunction "2_2") (pintype "unspecified"))
      (node (ref "TB6") (pin "1") (pinfunction "AO1_1") (pintype "unspecified"))
      (node (ref "TB6") (pin "2") (pinfunction "AO1_2") (pintype "unspecified"))
    )
    (net (code "35") (name "Net-(P12-Pad1)") (class "Default")
      (node (ref "P12") (pin "1") (pinfunction "1_1") (pintype "unspecified"))
      (node (ref "TB6") (pin "11") (pinfunction "BO1_11") (pintype "unspecified"))
      (node (ref "TB6") (pin "12") (pinfunction "BO1_12") (pintype "unspecified"))
    )
    (net (code "36") (name "Net-(P12-Pad2)") (class "Default")
      (node (ref "P12") (pin "2") (pinfunction "2_2") (pintype "unspecified"))
      (node (ref "TB6") (pin "7") (pinfunction "BO2_7") (pintype "unspecified"))
      (node (ref "TB6") (pin "8") (pinfunction "BO2_8") (pintype "unspecified"))
    )
    (net (code "37") (name "Net-(P13-Pad1)") (class "Default")
      (node (ref "P13") (pin "1") (pinfunction "1_1") (pintype "unspecified"))
      (node (ref "TB7") (pin "5") (pinfunction "AO2_5") (pintype "unspecified"))
      (node (ref "TB7") (pin "6") (pinfunction "AO2_6") (pintype "unspecified"))
    )
    (net (code "38") (name "Net-(P13-Pad2)") (class "Default")
      (node (ref "P13") (pin "2") (pinfunction "2_2") (pintype "unspecified"))
      (node (ref "TB7") (pin "1") (pinfunction "AO1_1") (pintype "unspecified"))
      (node (ref "TB7") (pin "2") (pinfunction "AO1_2") (pintype "unspecified"))
    )
    (net (code "39") (name "Net-(P14-Pad1)") (class "Default")
      (node (ref "P14") (pin "1") (pinfunction "1_1") (pintype "unspecified"))
      (node (ref "TB7") (pin "11") (pinfunction "BO1_11") (pintype "unspecified"))
      (node (ref "TB7") (pin "12") (pinfunction "BO1_12") (pintype "unspecified"))
    )
    (net (code "40") (name "Net-(P14-Pad2)") (class "Default")
      (node (ref "P14") (pin "2") (pinfunction "2_2") (pintype "unspecified"))
      (node (ref "TB7") (pin "7") (pinfunction "BO2_7") (pintype "unspecified"))
      (node (ref "TB7") (pin "8") (pinfunction "BO2_8") (pintype "unspecified"))
    )
    (net (code "41") (name "Net-(P15-Pad1)") (class "Default")
      (node (ref "P15") (pin "1") (pinfunction "1_1") (pintype "unspecified"))
      (node (ref "TB8") (pin "5") (pinfunction "AO2_5") (pintype "unspecified"))
      (node (ref "TB8") (pin "6") (pinfunction "AO2_6") (pintype "unspecified"))
    )
    (net (code "42") (name "Net-(P15-Pad2)") (class "Default")
      (node (ref "P15") (pin "2") (pinfunction "2_2") (pintype "unspecified"))
      (node (ref "TB8") (pin "1") (pinfunction "AO1_1") (pintype "unspecified"))
      (node (ref "TB8") (pin "2") (pinfunction "AO1_2") (pintype "unspecified"))
    )
    (net (code "43") (name "Net-(P16-Pad1)") (class "Default")
      (node (ref "P16") (pin "1") (pinfunction "1_1") (pintype "unspecified"))
      (node (ref "TB8") (pin "11") (pinfunction "BO1_11") (pintype "unspecified"))
      (node (ref "TB8") (pin "12") (pinfunction "BO1_12") (pintype "unspecified"))
    )
    (net (code "44") (name "Net-(P16-Pad2)") (class "Default")
      (node (ref "P16") (pin "2") (pinfunction "2_2") (pintype "unspecified"))
      (node (ref "TB8") (pin "7") (pinfunction "BO2_7") (pintype "unspecified"))
      (node (ref "TB8") (pin "8") (pinfunction "BO2_8") (pintype "unspecified"))
    )
    (net (code "45") (name "P20{slash}1") (class "Default")
      (node (ref "MCP20") (pin "21") (pinfunction "GPA0_21") (pintype "unspecified"))
      (node (ref "TB1") (pin "23") (pinfunction "PWMA_23") (pintype "unspecified"))
    )
    (net (code "46") (name "P20{slash}2") (class "Default")
      (node (ref "MCP20") (pin "22") (pinfunction "GPA1_22") (pintype "unspecified"))
      (node (ref "TB1") (pin "15") (pinfunction "PWMB_15") (pintype "unspecified"))
    )
    (net (code "47") (name "P20{slash}3") (class "Default")
      (node (ref "MCP20") (pin "23") (pinfunction "GPA2_23") (pintype "unspecified"))
      (node (ref "TB2") (pin "23") (pinfunction "PWMA_23") (pintype "unspecified"))
    )
    (net (code "48") (name "P20{slash}4") (class "Default")
      (node (ref "MCP20") (pin "24") (pinfunction "GPA3_24") (pintype "unspecified"))
      (node (ref "TB2") (pin "15") (pinfunction "PWMB_15") (pintype "unspecified"))
    )
    (net (code "49") (name "P20{slash}5") (class "Default")
      (node (ref "MCP20") (pin "25") (pinfunction "GPA4_25") (pintype "unspecified"))
      (node (ref "TB3") (pin "23") (pinfunction "PWMA_23") (pintype "unspecified"))
    )
    (net (code "50") (name "P20{slash}6") (class "Default")
      (node (ref "MCP20") (pin "26") (pinfunction "GPA5_26") (pintype "unspecified"))
      (node (ref "TB3") (pin "15") (pinfunction "PWMB_15") (pintype "unspecified"))
    )
    (net (code "51") (name "P20{slash}7") (class "Default")
      (node (ref "MCP20") (pin "27") (pinfunction "GPA6_27") (pintype "unspecified"))
      (node (ref "TB4") (pin "23") (pinfunction "PWMA_23") (pintype "unspecified"))
    )
    (net (code "52") (name "P20{slash}8") (class "Default")
      (node (ref "MCP20") (pin "28") (pinfunction "GPA7_28") (pintype "unspecified"))
      (node (ref "TB4") (pin "15") (pinfunction "PWMB_15") (pintype "unspecified"))
    )
    (net (code "53") (name "P20{slash}9") (class "Default")
      (node (ref "MCP20") (pin "1") (pinfunction "GPB0_1") (pintype "unspecified"))
      (node (ref "TB5") (pin "23") (pinfunction "PWMA_23") (pintype "unspecified"))
    )
    (net (code "54") (name "P20{slash}10") (class "Default")
      (node (ref "MCP20") (pin "2") (pinfunction "GPB1_2") (pintype "unspecified"))
      (node (ref "TB5") (pin "15") (pinfunction "PWMB_15") (pintype "unspecified"))
    )
    (net (code "55") (name "P20{slash}11") (class "Default")
      (node (ref "MCP20") (pin "3") (pinfunction "GPB2_3") (pintype "unspecified"))
      (node (ref "TB6") (pin "23") (pinfunction "PWMA_23") (pintype "unspecified"))
    )
    (net (code "56") (name "P20{slash}12") (class "Default")
      (node (ref "MCP20") (pin "4") (pinfunction "GPB3_4") (pintype "unspecified"))
      (node (ref "TB6") (pin "15") (pinfunction "PWMB_15") (pintype "unspecified"))
    )
    (net (code "57") (name "P20{slash}13") (class "Default")
      (node (ref "MCP20") (pin "5") (pinfunction "GPB4_5") (pintype "unspecified"))
      (node (ref "TB7") (pin "23") (pinfunction "PWMA_23") (pintype "unspecified"))
    )
    (net (code "58") (name "P20{slash}14") (class "Default")
      (node (ref "MCP20") (pin "6") (pinfunction "GPB5_6") (pintype "unspecified"))
      (node (ref "TB7") (pin "15") (pinfunction "PWMB_15") (pintype "unspecified"))
    )
    (net (code "59") (name "P20{slash}15") (class "Default")
      (node (ref "MCP20") (pin "7") (pinfunction "GPB6_7") (pintype "unspecified"))
      (node (ref "TB8") (pin "23") (pinfunction "PWMA_23") (pintype "unspecified"))
    )
    (net (code "60") (name "P20{slash}16") (class "Default")
      (node (ref "MCP20") (pin "8") (pinfunction "GPB7_8") (pintype "unspecified"))
      (node (ref "TB8") (pin "15") (pinfunction "PWMB_15") (pintype "unspecified"))
    )
    (net (code "61") (name "STBY1") (class "Default")
      (node (ref "R1") (pin "1") (pinfunction "1_1") (pintype "input"))
      (node (ref "TB1") (pin "19") (pinfunction "STBY_19") (pintype "unspecified"))
      (node (ref "TB2") (pin "19") (pinfunction "STBY_19") (pintype "unspecified"))
    )
    (net (code "62") (name "STBY2") (class "Default")
      (node (ref "R2") (pin "1") (pinfunction "1_1") (pintype "input"))
      (node (ref "TB3") (pin "19") (pinfunction "STBY_19") (pintype "unspecified"))
      (node (ref "TB4") (pin "19") (pinfunction "STBY_19") (pintype "unspecified"))
    )
    (net (code "63") (name "STBY3") (class "Default")
      (node (ref "R3") (pin "1") (pinfunction "1_1") (pintype "input"))
      (node (ref "TB5") (pin "19") (pinfunction "STBY_19") (pintype "unspecified"))
      (node (ref "TB6") (pin "19") (pinfunction "STBY_19") (pintype "unspecified"))
    )
    (net (code "64") (name "STBY4") (class "Default")
      (node (ref "R4") (pin "1") (pinfunction "1_1") (pintype "input"))
      (node (ref "TB7") (pin "19") (pinfunction "STBY_19") (pintype "unspecified"))
      (node (ref "TB8") (pin "19") (pinfunction "STBY_19") (pintype "unspecified"))
    )
    (net (code "65") (name "unconnected-(MCP20-INTA-Pad20)") (class "Default")
      (node (ref "MCP20") (pin "20") (pinfunction "INTA_20") (pintype "unspecified+no_connect"))
    )
    (net (code "66") (name "unconnected-(MCP20-INTB-Pad19)") (class "Default")
      (node (ref "MCP20") (pin "19") (pinfunction "INTB_19") (pintype "unspecified+no_connect"))
    )
    (net (code "67") (name "unconnected-(MCP20-NC-Pad11)") (class "Default")
      (node (ref "MCP20") (pin "11") (pinfunction "NC_11") (pintype "unspecified+no_connect"))
    )
    (net (code "68") (name "unconnected-(MCP20-NC-Pad14)") (class "Default")
      (node (ref "MCP20") (pin "14") (pinfunction "NC_14") (pintype "unspecified+no_connect"))
    )
    (net (code "69") (name "unconnected-(RPI1-DNC-Pad27)") (class "Default")
      (node (ref "RPI1") (pin "27") (pinfunction "DNC_27") (pintype "unspecified+no_connect"))
    )
    (net (code "70") (name "unconnected-(RPI1-DNC-Pad28)") (class "Default")
      (node (ref "RPI1") (pin "28") (pinfunction "DNC_28") (pintype "unspecified+no_connect"))
    )
    (net (code "71") (name "unconnected-(RPI1-GPIO4-Pad7)") (class "Default")
      (node (ref "RPI1") (pin "7") (pinfunction "GPIO4_7") (pintype "unspecified+no_connect"))
    )
    (net (code "72") (name "unconnected-(RPI1-GPIO5-Pad29)") (class "Default")
      (node (ref "RPI1") (pin "29") (pinfunction "GPIO5_29") (pintype "unspecified+no_connect"))
    )
    (net (code "73") (name "unconnected-(RPI1-GPIO6-Pad31)") (class "Default")
      (node (ref "RPI1") (pin "31") (pinfunction "GPIO6_31") (pintype "unspecified+no_connect"))
    )
    (net (code "74") (name "unconnected-(RPI1-GPIO7-Pad26)") (class "Default")
      (node (ref "RPI1") (pin "26") (pinfunction "GPIO7_26") (pintype "unspecified+no_connect"))
    )
    (net (code "75") (name "unconnected-(RPI1-GPIO8-Pad24)") (class "Default")
      (node (ref "RPI1") (pin "24") (pinfunction "GPIO8_24") (pintype "unspecified+no_connect"))
    )
    (net (code "76") (name "unconnected-(RPI1-GPIO9-Pad21)") (class "Default")
      (node (ref "RPI1") (pin "21") (pinfunction "GPIO9_21") (pintype "unspecified+no_connect"))
    )
    (net (code "77") (name "unconnected-(RPI1-GPIO10-Pad19)") (class "Default")
      (node (ref "RPI1") (pin "19") (pinfunction "GPIO10_19") (pintype "unspecified+no_connect"))
    )
    (net (code "78") (name "unconnected-(RPI1-GPIO11-Pad23)") (class "Default")
      (node (ref "RPI1") (pin "23") (pinfunction "GPIO11_23") (pintype "unspecified+no_connect"))
    )
    (net (code "79") (name "unconnected-(RPI1-GPIO12-Pad32)") (class "Default")
      (node (ref "RPI1") (pin "32") (pinfunction "GPIO12_32") (pintype "unspecified+no_connect"))
    )
    (net (code "80") (name "unconnected-(RPI1-GPIO13-Pad33)") (class "Default")
      (node (ref "RPI1") (pin "33") (pinfunction "GPIO13_33") (pintype "unspecified+no_connect"))
    )
    (net (code "81") (name "unconnected-(RPI1-GPIO14-Pad8)") (class "Default")
      (node (ref "RPI1") (pin "8") (pinfunction "GPIO14_8") (pintype "unspecified+no_connect"))
    )
    (net (code "82") (name "unconnected-(RPI1-GPIO15-Pad10)") (class "Default")
      (node (ref "RPI1") (pin "10") (pinfunction "GPIO15_10") (pintype "unspecified+no_connect"))
    )
    (net (code "83") (name "unconnected-(RPI1-GPIO16-Pad36)") (class "Default")
      (node (ref "RPI1") (pin "36") (pinfunction "GPIO16_36") (pintype "unspecified+no_connect"))
    )
    (net (code "84") (name "unconnected-(RPI1-GPIO18-Pad12)") (class "Default")
      (node (ref "RPI1") (pin "12") (pinfunction "GPIO18_12") (pintype "unspecified+no_connect"))
    )
    (net (code "85") (name "unconnected-(RPI1-GPIO19-Pad35)") (class "Default")
      (node (ref "RPI1") (pin "35") (pinfunction "GPIO19_35") (pintype "unspecified+no_connect"))
    )
    (net (code "86") (name "unconnected-(RPI1-GPIO20-Pad38)") (class "Default")
      (node (ref "RPI1") (pin "38") (pinfunction "GPIO20_38") (pintype "unspecified+no_connect"))
    )
    (net (code "87") (name "unconnected-(RPI1-GPIO21-Pad40)") (class "Default")
      (node (ref "RPI1") (pin "40") (pinfunction "GPIO21_40") (pintype "unspecified+no_connect"))
    )
    (net (code "88") (name "unconnected-(RPI1-GPIO23-Pad16)") (class "Default")
      (node (ref "RPI1") (pin "16") (pinfunction "GPIO23_16") (pintype "unspecified+no_connect"))
    )
    (net (code "89") (name "unconnected-(RPI1-GPIO24-Pad18)") (class "Default")
      (node (ref "RPI1") (pin "18") (pinfunction "GPIO24_18") (pintype "unspecified+no_connect"))
    )
    (net (code "90") (name "unconnected-(RPI1-GPIO25-Pad22)") (class "Default")
      (node (ref "RPI1") (pin "22") (pinfunction "GPIO25_22") (pintype "unspecified+no_connect"))
    )
    (net (code "91") (name "unconnected-(RPI1-GPIO26-Pad37)") (class "Default")
      (node (ref "RPI1") (pin "37") (pinfunction "GPIO26_37") (pintype "unspecified+no_connect"))
    )
  )
)
